# NanjaTown02_switch.net
KiCad netlist of a schematic drawn in EAGLE
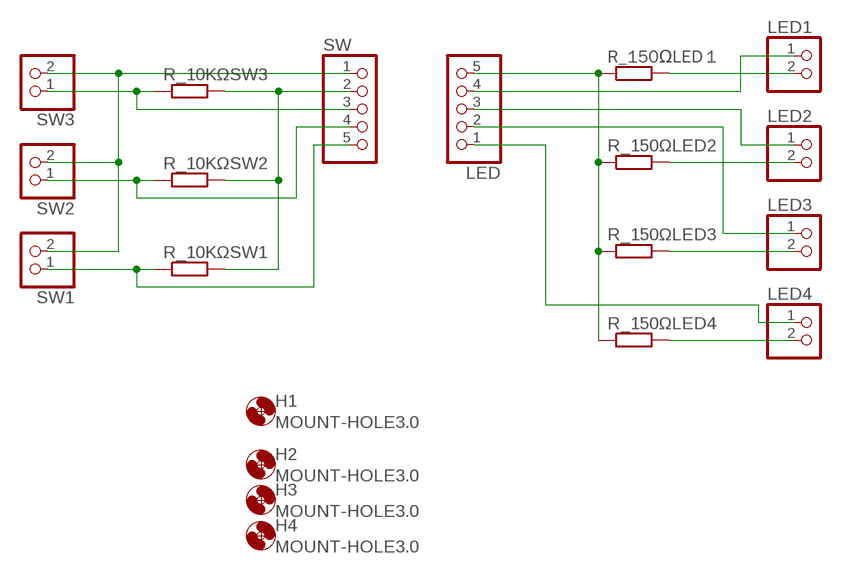
[diagram p0: schematic, sheet 1]

(export (version "E")
  (design (tool "Eeschema 10.0.6"))
  (components
    (comp (ref "H1")
      (value "MOUNT-HOLE3.0")
      (footprint "eagle-import:3,0")
      (libsource (lib "eagle-import") (part "MOUNT-HOLE3.0"))
    )
    (comp (ref "H2")
      (value "MOUNT-HOLE3.0")
      (footprint "eagle-import:3,0")
      (libsource (lib "eagle-import") (part "MOUNT-HOLE3.0"))
    )
    (comp (ref "H3")
      (value "MOUNT-HOLE3.0")
      (footprint "eagle-import:3,0")
      (libsource (lib "eagle-import") (part "MOUNT-HOLE3.0"))
    )
    (comp (ref "H4")
      (value "MOUNT-HOLE3.0")
      (footprint "eagle-import:3,0")
      (libsource (lib "eagle-import") (part "MOUNT-HOLE3.0"))
    )
    (comp (ref "LED")
      (value "PINHD-1X5")
      (footprint "eagle-import:1X05")
      (libsource (lib "eagle-import") (part "PINHD-1X5"))
    )
    (comp (ref "LED1")
      (value "PINHD-1X2")
      (footprint "eagle-import:1X02")
      (libsource (lib "eagle-import") (part "PINHD-1X2"))
    )
    (comp (ref "LED2")
      (value "PINHD-1X2")
      (footprint "eagle-import:1X02")
      (libsource (lib "eagle-import") (part "PINHD-1X2"))
    )
    (comp (ref "LED3")
      (value "PINHD-1X2")
      (footprint "eagle-import:1X02")
      (libsource (lib "eagle-import") (part "PINHD-1X2"))
    )
    (comp (ref "LED4")
      (value "PINHD-1X2")
      (footprint "eagle-import:1X02")
      (libsource (lib "eagle-import") (part "PINHD-1X2"))
    )
    (comp (ref "R_10KΩSW1")
      (value "R-EU_0207/10")
      (footprint "eagle-import:0207_10")
      (libsource (lib "eagle-import") (part "R-EU_0207/10"))
    )
    (comp (ref "R_10KΩSW2")
      (value "R-EU_0207/10")
      (footprint "eagle-import:0207_10")
      (libsource (lib "eagle-import") (part "R-EU_0207/10"))
    )
    (comp (ref "R_10KΩSW3")
      (value "R-EU_0207/10")
      (footprint "eagle-import:0207_10")
      (libsource (lib "eagle-import") (part "R-EU_0207/10"))
    )
    (comp (ref "R_150ΩLED2")
      (value "R-EU_0207/10")
      (footprint "eagle-import:0207_10")
      (libsource (lib "eagle-import") (part "R-EU_0207/10"))
    )
    (comp (ref "R_150ΩLED3")
      (value "R-EU_0207/10")
      (footprint "eagle-import:0207_10")
      (libsource (lib "eagle-import") (part "R-EU_0207/10"))
    )
    (comp (ref "R_150ΩLED4")
      (value "R-EU_0207/10")
      (footprint "eagle-import:0207_10")
      (libsource (lib "eagle-import") (part "R-EU_0207/10"))
    )
    (comp (ref "R_150ΩLED１")
      (value "R-EU_0207/10")
      (footprint "eagle-import:0207_10")
      (libsource (lib "eagle-import") (part "R-EU_0207/10"))
    )
    (comp (ref "SW")
      (value "PINHD-1X5")
      (footprint "eagle-import:1X05")
      (libsource (lib "eagle-import") (part "PINHD-1X5"))
    )
    (comp (ref "SW1")
      (value "PINHD-1X2")
      (footprint "eagle-import:1X02")
      (libsource (lib "eagle-import") (part "PINHD-1X2"))
    )
    (comp (ref "SW2")
      (value "PINHD-1X2")
      (footprint "eagle-import:1X02")
      (libsource (lib "eagle-import") (part "PINHD-1X2"))
    )
    (comp (ref "SW3")
      (value "PINHD-1X2")
      (footprint "eagle-import:1X02")
      (libsource (lib "eagle-import") (part "PINHD-1X2"))
    )
  )
  (nets
    (net (code "1") (name "Net-(LED-Pad1)") (class "Default")
      (node (ref "LED") (pin "1") (pinfunction "1_1") (pintype "passive"))
      (node (ref "LED4") (pin "1") (pinfunction "1_1") (pintype "passive"))
    )
    (net (code "2") (name "Net-(LED-Pad2)") (class "Default")
      (node (ref "LED") (pin "2") (pinfunction "2_2") (pintype "passive"))
      (node (ref "LED3") (pin "1") (pinfunction "1_1") (pintype "passive"))
    )
    (net (code "3") (name "Net-(LED-Pad3)") (class "Default")
      (node (ref "LED") (pin "3") (pinfunction "3_3") (pintype "passive"))
      (node (ref "LED2") (pin "1") (pinfunction "1_1") (pintype "passive"))
    )
    (net (code "4") (name "Net-(LED-Pad4)") (class "Default")
      (node (ref "LED") (pin "4") (pinfunction "4_4") (pintype "passive"))
      (node (ref "LED1") (pin "1") (pinfunction "1_1") (pintype "passive"))
    )
    (net (code "5") (name "Net-(LED-Pad5)") (class "Default")
      (node (ref "LED") (pin "5") (pinfunction "5_5") (pintype "passive"))
      (node (ref "R_150ΩLED2") (pin "1") (pinfunction "1_1") (pintype "passive"))
      (node (ref "R_150ΩLED3") (pin "1") (pinfunction "1_1") (pintype "passive"))
      (node (ref "R_150ΩLED4") (pin "1") (pinfunction "1_1") (pintype "passive"))
      (node (ref "R_150ΩLED１") (pin "1") (pinfunction "1_1") (pintype "passive"))
    )
    (net (code "6") (name "Net-(LED1-Pad2)") (class "Default")
      (node (ref "LED1") (pin "2") (pinfunction "2_2") (pintype "passive"))
      (node (ref "R_150ΩLED１") (pin "2") (pinfunction "2_2") (pintype "passive"))
    )
    (net (code "7") (name "Net-(LED2-Pad2)") (class "Default")
      (node (ref "LED2") (pin "2") (pinfunction "2_2") (pintype "passive"))
      (node (ref "R_150ΩLED2") (pin "2") (pinfunction "2_2") (pintype "passive"))
    )
    (net (code "8") (name "Net-(LED3-Pad2)") (class "Default")
      (node (ref "LED3") (pin "2") (pinfunction "2_2") (pintype "passive"))
      (node (ref "R_150ΩLED3") (pin "2") (pinfunction "2_2") (pintype "passive"))
    )
    (net (code "9") (name "Net-(LED4-Pad2)") (class "Default")
      (node (ref "LED4") (pin "2") (pinfunction "2_2") (pintype "passive"))
      (node (ref "R_150ΩLED4") (pin "2") (pinfunction "2_2") (pintype "passive"))
    )
    (net (code "10") (name "Net-(R_10KΩSW1-Pad1)") (class "Default")
      (node (ref "R_10KΩSW1") (pin "1") (pinfunction "1_1") (pintype "passive"))
      (node (ref "SW") (pin "5") (pinfunction "5_5") (pintype "passive"))
      (node (ref "SW1") (pin "1") (pinfunction "1_1") (pintype "passive"))
    )
    (net (code "11") (name "Net-(R_10KΩSW1-Pad2)") (class "Default")
      (node (ref "R_10KΩSW1") (pin "2") (pinfunction "2_2") (pintype "passive"))
      (node (ref "R_10KΩSW2") (pin "2") (pinfunction "2_2") (pintype "passive"))
      (node (ref "R_10KΩSW3") (pin "2") (pinfunction "2_2") (pintype "passive"))
      (node (ref "SW") (pin "2") (pinfunction "2_2") (pintype "passive"))
    )
    (net (code "12") (name "Net-(R_10KΩSW2-Pad1)") (class "Default")
      (node (ref "R_10KΩSW2") (pin "1") (pinfunction "1_1") (pintype "passive"))
      (node (ref "SW") (pin "4") (pinfunction "4_4") (pintype "passive"))
      (node (ref "SW2") (pin "1") (pinfunction "1_1") (pintype "passive"))
    )
    (net (code "13") (name "Net-(R_10KΩSW3-Pad1)") (class "Default")
      (node (ref "R_10KΩSW3") (pin "1") (pinfunction "1_1") (pintype "passive"))
      (node (ref "SW") (pin "3") (pinfunction "3_3") (pintype "passive"))
      (node (ref "SW3") (pin "1") (pinfunction "1_1") (pintype "passive"))
    )
    (net (code "14") (name "Net-(SW-Pad1)") (class "Default")
      (node (ref "SW") (pin "1") (pinfunction "1_1") (pintype "passive"))
      (node (ref "SW1") (pin "2") (pinfunction "2_2") (pintype "passive"))
      (node (ref "SW2") (pin "2") (pinfunction "2_2") (pintype "passive"))
      (node (ref "SW3") (pin "2") (pinfunction "2_2") (pintype "passive"))
    )
  )
)
